# Input_Power.net
KiCad netlist of a schematic drawn in Altium Designer
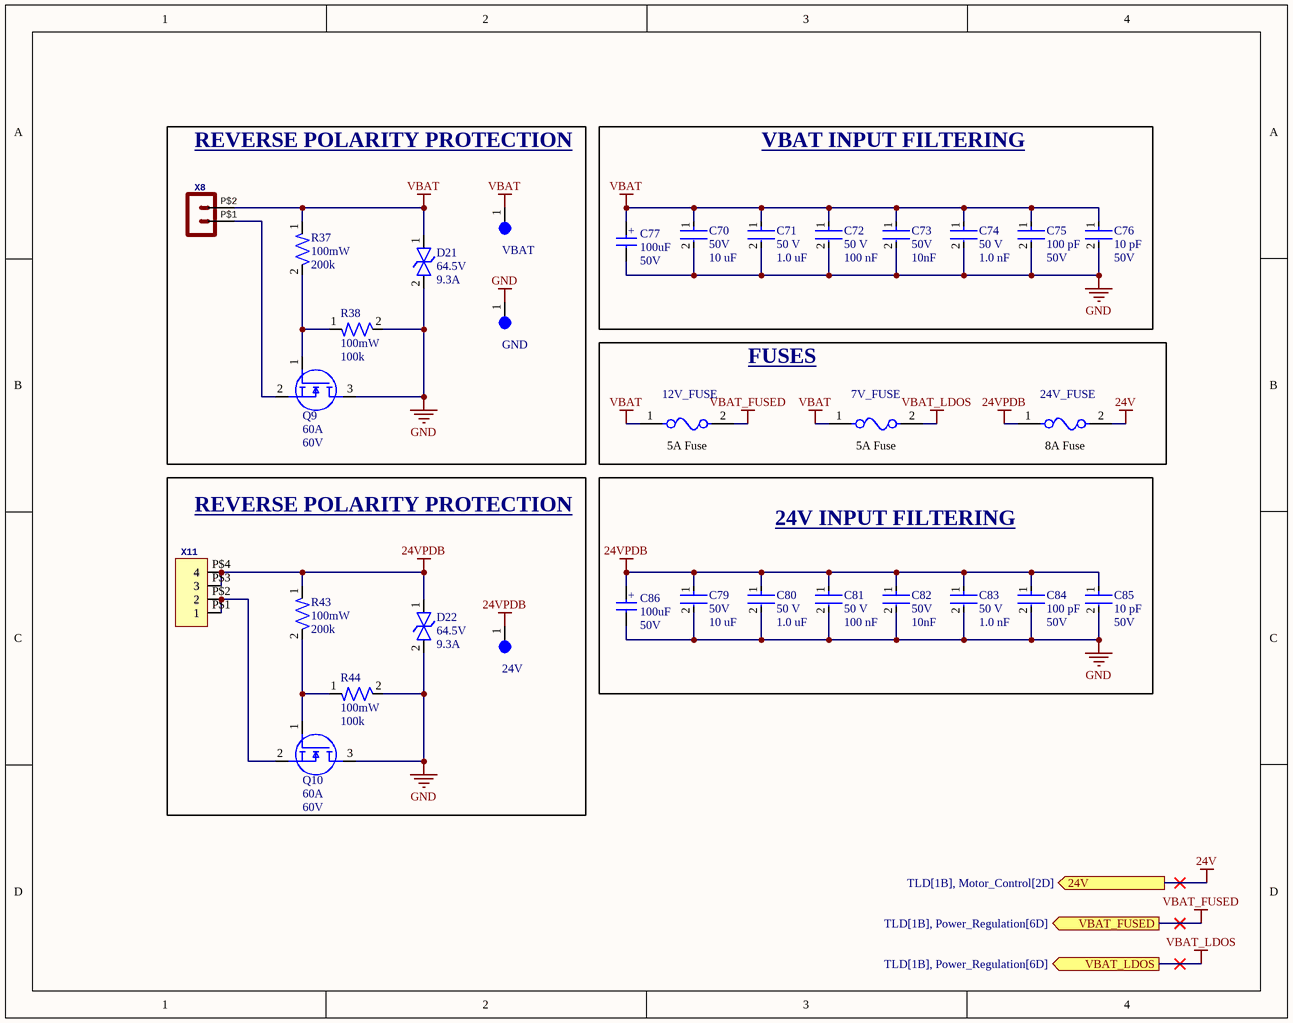
[diagram p0: Input_Power.SchDoc]

(export (version "E")
  (design (tool "Eeschema 10.0.6"))
  (components
    (comp (ref "7V_FUSE")
      (value "01550900M")
      (footprint "FUSE-0001")
      (description "FUSE BLOK CARTRIDGE 125V 10A SMD")
      (libsource (lib "JLC_25") (part "FUSE-0001"))
    )
    (comp (ref "12V_FUSE")
      (value "01550900M")
      (footprint "FUSE-0001")
      (description "FUSE BLOK CARTRIDGE 125V 10A SMD")
      (libsource (lib "JLC_25") (part "FUSE-0001"))
    )
    (comp (ref "24V")
      (value "5003")
      (footprint "TEST-POINT-0001")
      (description "Oranange PC Test Point, Miniature Phoisphor Bronze Silver Plating Through Hole Mounting Type")
      (libsource (lib "*") (part "TEST-POINT-0001"))
    )
    (comp (ref "24V_FUSE")
      (value "01550900M")
      (footprint "FUSE-0001")
      (description "FUSE BLOK CARTRIDGE 125V 10A SMD")
      (libsource (lib "JLC_25") (part "FUSE-0001"))
    )
    (comp (ref "C70")
      (value "CL32B106KBJNNNE")
      (footprint "CAP-1210")
      (description "CAP CER 10UF 50V X7R 1210")
      (fields (field (name "VOLTAGE") "50V") (field (name "CAPACITANCE") "10 uF"))
      (libsource (lib "JLC_25") (part "CAP-10U-0002"))
    )
    (comp (ref "C71")
      (value "CC0805KKX7R9BB105")
      (footprint "CAP-0805")
      (description "CAP CER 1UF 50V X7R 0805")
      (fields (field (name "VOLTAGE") "50 V") (field (name "CAPACITANCE") "1.0 uF"))
      (libsource (lib "JLC_25") (part "CAP-1U-0001"))
    )
    (comp (ref "C72")
      (value "CC0805KRX7R9BB104")
      (footprint "CAP-0805")
      (description "CAP CER 0.1UF 50V X7R 0805")
      (fields (field (name "VOLTAGE RATING") "50 V") (field (name "CAPACITANCE") "100 nF"))
      (libsource (lib "JLC_25") (part "CAP-0.1U-0002"))
    )
    (comp (ref "C73")
      (value "GRM2195C1H103JA01D")
      (footprint "CAP-0805")
      (description "CAP CER 10000PF 50V C0G/NP0 0805")
      (fields (field (name "VOLTAGE") "50V") (field (name "CAPACITANCE") "10nF"))
      (libsource (lib "JLC_25") (part "CAP-10N-0001"))
    )
    (comp (ref "C74")
      (value "CC0402KRX7R9BB102")
      (footprint "CAP-0402")
      (description "CAP CER 1000PF 50V X7R 0402")
      (fields (field (name "VOLTAGE") "50 V") (field (name "CAPACITANCE") "1.0 nF"))
      (libsource (lib "JLC_25") (part "CAP-1N-0001"))
    )
    (comp (ref "C75")
      (value "CC0402JRNPO9BN101")
      (footprint "CAP-0402")
      (description "CAP CER 100PF 50V C0G/NPO 0402")
      (fields (field (name "CAPACITANCE") "100 pF") (field (name "VOLTAGE") "50V"))
      (libsource (lib "JLC_25") (part "CAP-100P-0001"))
    )
    (comp (ref "C76")
      (value "CC0402JRNPO9BN100")
      (footprint "CAP-0402")
      (description "CAP CER 10PF 50V C0G/NPO 0402")
      (fields (field (name "CAPACITANCE") "10 pF") (field (name "VOLTAGE") "50V"))
      (libsource (lib "JLC_25") (part "CAP-10P-0001"))
    )
    (comp (ref "C77")
      (value "860040674004")
      (footprint "WCAP-ATUL_8X11.5(DXL)")
      (description "100 µF 50 V Aluminum Electrolytic Capacitors Radial, Can 7000 Hrs @ 105°C")
      (fields
        (field (name "MF") "{'manufacturer': u'~{W}xfcrth Elektronik'}")
        (field (name "CAPACITANCE") "100uF")
        (field (name "VOLTAGE") "50V")
      )
      (libsource (lib "MasterLib") (part "CAP-100u-0001"))
    )
    (comp (ref "C79")
      (value "CL32B106KBJNNNE")
      (footprint "CAP-1210")
      (description "CAP CER 10UF 50V X7R 1210")
      (fields (field (name "VOLTAGE") "50V") (field (name "CAPACITANCE") "10 uF"))
      (libsource (lib "JLC_25") (part "CAP-10U-0002"))
    )
    (comp (ref "C80")
      (value "CC0805KKX7R9BB105")
      (footprint "CAP-0805")
      (description "CAP CER 1UF 50V X7R 0805")
      (fields (field (name "VOLTAGE") "50 V") (field (name "CAPACITANCE") "1.0 uF"))
      (libsource (lib "JLC_25") (part "CAP-1U-0001"))
    )
    (comp (ref "C81")
      (value "CC0805KRX7R9BB104")
      (footprint "CAP-0805")
      (description "CAP CER 0.1UF 50V X7R 0805")
      (fields (field (name "VOLTAGE RATING") "50 V") (field (name "CAPACITANCE") "100 nF"))
      (libsource (lib "JLC_25") (part "CAP-0.1U-0002"))
    )
    (comp (ref "C82")
      (value "GRM2195C1H103JA01D")
      (footprint "CAP-0805")
      (description "CAP CER 10000PF 50V C0G/NP0 0805")
      (fields (field (name "VOLTAGE") "50V") (field (name "CAPACITANCE") "10nF"))
      (libsource (lib "JLC_25") (part "CAP-10N-0001"))
    )
    (comp (ref "C83")
      (value "CC0402KRX7R9BB102")
      (footprint "CAP-0402")
      (description "CAP CER 1000PF 50V X7R 0402")
      (fields (field (name "VOLTAGE") "50 V") (field (name "CAPACITANCE") "1.0 nF"))
      (libsource (lib "JLC_25") (part "CAP-1N-0001"))
    )
    (comp (ref "C84")
      (value "CC0402JRNPO9BN101")
      (footprint "CAP-0402")
      (description "CAP CER 100PF 50V C0G/NPO 0402")
      (fields (field (name "CAPACITANCE") "100 pF") (field (name "VOLTAGE") "50V"))
      (libsource (lib "JLC_25") (part "CAP-100P-0001"))
    )
    (comp (ref "C85")
      (value "CC0402JRNPO9BN100")
      (footprint "CAP-0402")
      (description "CAP CER 10PF 50V C0G/NPO 0402")
      (fields (field (name "CAPACITANCE") "10 pF") (field (name "VOLTAGE") "50V"))
      (libsource (lib "JLC_25") (part "CAP-10P-0001"))
    )
    (comp (ref "C86")
      (value "860040674004")
      (footprint "WCAP-ATUL_8X11.5(DXL)")
      (description "100 µF 50 V Aluminum Electrolytic Capacitors Radial, Can 7000 Hrs @ 105°C")
      (fields
        (field (name "MF") "{'manufacturer': u'~{W}xfcrth Elektronik'}")
        (field (name "CAPACITANCE") "100uF")
        (field (name "VOLTAGE") "50V")
      )
      (libsource (lib "MasterLib") (part "CAP-100u-0001"))
    )
    (comp (ref "D21")
      (value "SMBJ40CA")
      (footprint "DO-214AA (SMBJ)")
      (description "TVS DIODE 40VWM 64.5VC DO214AA")
      (fields (field (name "VOLTAGE RATING") "64.5V") (field (name "CURRENT RATING") "9.3A"))
      (libsource (lib "JLC_25") (part "DIO-TVS-0001"))
    )
    (comp (ref "D22")
      (value "SMBJ40CA")
      (footprint "DO-214AA (SMBJ)")
      (description "TVS DIODE 40VWM 64.5VC DO214AA")
      (fields (field (name "VOLTAGE RATING") "64.5V") (field (name "CURRENT RATING") "9.3A"))
      (libsource (lib "JLC_25") (part "DIO-TVS-0001"))
    )
    (comp (ref "GND")
      (value "5003")
      (footprint "TEST-POINT-0001")
      (description "Oranange PC Test Point, Miniature Phoisphor Bronze Silver Plating Through Hole Mounting Type")
      (libsource (lib "*") (part "TEST-POINT-0001"))
    )
    (comp (ref "Q9")
      (value "CSD18543Q3AT")
      (footprint "IC-8VSONCLIP")
      (description "MOSFET N-CH 60V 12A/60A 8VSON")
      (fields (field (name "VOLTAGE") "60V") (field (name "CONTINUOUS CURRENT") "60A"))
      (libsource (lib "JLC_25") (part "NMOS-60A-0001"))
    )
    (comp (ref "Q10")
      (value "CSD18543Q3AT")
      (footprint "IC-8VSONCLIP")
      (description "MOSFET N-CH 60V 12A/60A 8VSON")
      (fields (field (name "VOLTAGE") "60V") (field (name "CONTINUOUS CURRENT") "60A"))
      (libsource (lib "JLC_25") (part "NMOS-60A-0001"))
    )
    (comp (ref "R37")
      (value "RC0603FR-07200KL")
      (footprint "RES-0603")
      (description "RES SMD 200K OHM 1% 1/10W 0603")
      (fields
        (field (name "TOLERANCE") "1%")
        (field (name "POWER") "100mW")
        (field (name "RESISTANCE") "200k")
      )
      (libsource (lib "JLC_25") (part "RES-200k-0001"))
    )
    (comp (ref "R38")
      (value "RC0603FR-07100KL")
      (footprint "RES-0603")
      (description "RES SMD 100K OHM 1% 1/10W 0603")
      (fields
        (field (name "TOLERANCE") "1%")
        (field (name "POWER") "100mW")
        (field (name "RESISTANCE") "100k")
      )
      (libsource (lib "JLC_25") (part "RES-100k-0001"))
    )
    (comp (ref "R43")
      (value "RC0603FR-07200KL")
      (footprint "RES-0603")
      (description "RES SMD 200K OHM 1% 1/10W 0603")
      (fields
        (field (name "TOLERANCE") "1%")
        (field (name "POWER") "100mW")
        (field (name "RESISTANCE") "200k")
      )
      (libsource (lib "JLC_25") (part "RES-200k-0001"))
    )
    (comp (ref "R44")
      (value "RC0603FR-07100KL")
      (footprint "RES-0603")
      (description "RES SMD 100K OHM 1% 1/10W 0603")
      (fields
        (field (name "TOLERANCE") "1%")
        (field (name "POWER") "100mW")
        (field (name "RESISTANCE") "100k")
      )
      (libsource (lib "JLC_25") (part "RES-100k-0001"))
    )
    (comp (ref "VBAT")
      (value "5003")
      (footprint "TEST-POINT-0001")
      (description "Oranange PC Test Point, Miniature Phoisphor Bronze Silver Plating Through Hole Mounting Type")
      (libsource (lib "*") (part "TEST-POINT-0001"))
    )
    (comp (ref "X8")
      (value "Molex - Micro-Fit 3.0 Series connector,  3.00mm (0.118\") pitch header, 2 positions.")
      (footprint "43045-0200")
      (libsource (lib "MasterLib") (part "HEADER_POS2_43045-0200"))
    )
    (comp (ref "X11")
      (value "Molex - Micro-Fit 3.0 Series connector,  3.00mm (0.118\") pitch header, 4 positions.")
      (footprint "43045-0400")
      (libsource (lib "Molex Microfit") (part "HEADER_POS4_?43045-0401"))
    )
  )
  (nets
    (net (code "1") (name "24V") (class "Default")
      (node (ref "24V_FUSE") (pin "2") (pinfunction "2_2") (pintype "passive"))
    )
    (net (code "2") (name "24VPDB") (class "Default")
      (node (ref "24V") (pin "1") (pinfunction "0_1") (pintype "passive"))
      (node (ref "24V_FUSE") (pin "1") (pinfunction "1_1") (pintype "passive"))
      (node (ref "C79") (pin "1") (pinfunction "1_1") (pintype "passive"))
      (node (ref "C80") (pin "1") (pinfunction "1_1") (pintype "passive"))
      (node (ref "C81") (pin "1") (pinfunction "1_1") (pintype "passive"))
      (node (ref "C82") (pin "1") (pinfunction "1_1") (pintype "passive"))
      (node (ref "C83") (pin "1") (pinfunction "1_1") (pintype "passive"))
      (node (ref "C84") (pin "1") (pinfunction "1_1") (pintype "passive"))
      (node (ref "C85") (pin "1") (pinfunction "1_1") (pintype "passive"))
      (node (ref "C86") (pin "1") (pinfunction "POS_1") (pintype "passive"))
      (node (ref "D22") (pin "1") (pintype "passive"))
      (node (ref "R43") (pin "1") (pinfunction "1_1") (pintype "passive"))
      (node (ref "X11") (pin "P$3") (pinfunction "3_P$3") (pintype "passive"))
      (node (ref "X11") (pin "P$4") (pinfunction "4_P$4") (pintype "passive"))
    )
    (net (code "3") (name "GND") (class "Default")
      (node (ref "C70") (pin "2") (pinfunction "2_2") (pintype "passive"))
      (node (ref "C71") (pin "2") (pinfunction "2_2") (pintype "passive"))
      (node (ref "C72") (pin "2") (pinfunction "2_2") (pintype "passive"))
      (node (ref "C73") (pin "2") (pinfunction "2_2") (pintype "passive"))
      (node (ref "C74") (pin "2") (pinfunction "2_2") (pintype "passive"))
      (node (ref "C75") (pin "2") (pinfunction "2_2") (pintype "passive"))
      (node (ref "C76") (pin "2") (pinfunction "2_2") (pintype "passive"))
      (node (ref "C77") (pin "2") (pinfunction "NEG_2") (pintype "passive"))
      (node (ref "C79") (pin "2") (pinfunction "2_2") (pintype "passive"))
      (node (ref "C80") (pin "2") (pinfunction "2_2") (pintype "passive"))
      (node (ref "C81") (pin "2") (pinfunction "2_2") (pintype "passive"))
      (node (ref "C82") (pin "2") (pinfunction "2_2") (pintype "passive"))
      (node (ref "C83") (pin "2") (pinfunction "2_2") (pintype "passive"))
      (node (ref "C84") (pin "2") (pinfunction "2_2") (pintype "passive"))
      (node (ref "C85") (pin "2") (pinfunction "2_2") (pintype "passive"))
      (node (ref "C86") (pin "2") (pinfunction "NEG_2") (pintype "passive"))
      (node (ref "D21") (pin "2") (pintype "passive"))
      (node (ref "D22") (pin "2") (pintype "passive"))
      (node (ref "GND") (pin "1") (pinfunction "0_1") (pintype "passive"))
      (node (ref "Q10") (pin "3") (pinfunction "D_3") (pintype "passive"))
      (node (ref "Q9") (pin "3") (pinfunction "D_3") (pintype "passive"))
      (node (ref "R38") (pin "2") (pinfunction "2_2") (pintype "passive"))
      (node (ref "R44") (pin "2") (pinfunction "2_2") (pintype "passive"))
    )
    (net (code "4") (name "Net-(Q9-G)") (class "Default")
      (node (ref "Q9") (pin "1") (pinfunction "G_1") (pintype "passive"))
      (node (ref "R37") (pin "2") (pinfunction "2_2") (pintype "passive"))
      (node (ref "R38") (pin "1") (pinfunction "1_1") (pintype "passive"))
    )
    (net (code "5") (name "Net-(Q9-S)") (class "Default")
      (node (ref "Q9") (pin "2") (pinfunction "S_2") (pintype "passive"))
      (node (ref "X8") (pin "P$1") (pinfunction "1_P$1") (pintype "passive"))
    )
    (net (code "6") (name "Net-(Q10-G)") (class "Default")
      (node (ref "Q10") (pin "1") (pinfunction "G_1") (pintype "passive"))
      (node (ref "R43") (pin "2") (pinfunction "2_2") (pintype "passive"))
      (node (ref "R44") (pin "1") (pinfunction "1_1") (pintype "passive"))
    )
    (net (code "7") (name "Net-(Q10-S)") (class "Default")
      (node (ref "Q10") (pin "2") (pinfunction "S_2") (pintype "passive"))
      (node (ref "X11") (pin "P$1") (pinfunction "1_P$1") (pintype "passive"))
      (node (ref "X11") (pin "P$2") (pinfunction "2_P$2") (pintype "passive"))
    )
    (net (code "8") (name "VBAT") (class "Default")
      (node (ref "12V_FUSE") (pin "1") (pinfunction "1_1") (pintype "passive"))
      (node (ref "7V_FUSE") (pin "1") (pinfunction "1_1") (pintype "passive"))
      (node (ref "C70") (pin "1") (pinfunction "1_1") (pintype "passive"))
      (node (ref "C71") (pin "1") (pinfunction "1_1") (pintype "passive"))
      (node (ref "C72") (pin "1") (pinfunction "1_1") (pintype "passive"))
      (node (ref "C73") (pin "1") (pinfunction "1_1") (pintype "passive"))
      (node (ref "C74") (pin "1") (pinfunction "1_1") (pintype "passive"))
      (node (ref "C75") (pin "1") (pinfunction "1_1") (pintype "passive"))
      (node (ref "C76") (pin "1") (pinfunction "1_1") (pintype "passive"))
      (node (ref "C77") (pin "1") (pinfunction "POS_1") (pintype "passive"))
      (node (ref "D21") (pin "1") (pintype "passive"))
      (node (ref "R37") (pin "1") (pinfunction "1_1") (pintype "passive"))
      (node (ref "VBAT") (pin "1") (pinfunction "0_1") (pintype "passive"))
      (node (ref "X8") (pin "P$2") (pinfunction "2_P$2") (pintype "passive"))
    )
    (net (code "9") (name "VBAT_FUSED") (class "Default")
      (node (ref "12V_FUSE") (pin "2") (pinfunction "2_2") (pintype "passive"))
    )
    (net (code "10") (name "VBAT_LDOS") (class "Default")
      (node (ref "7V_FUSE") (pin "2") (pinfunction "2_2") (pintype "passive"))
    )
  )
)
